# lcd-i2c.net
KiCad netlist of a schematic drawn in EAGLE
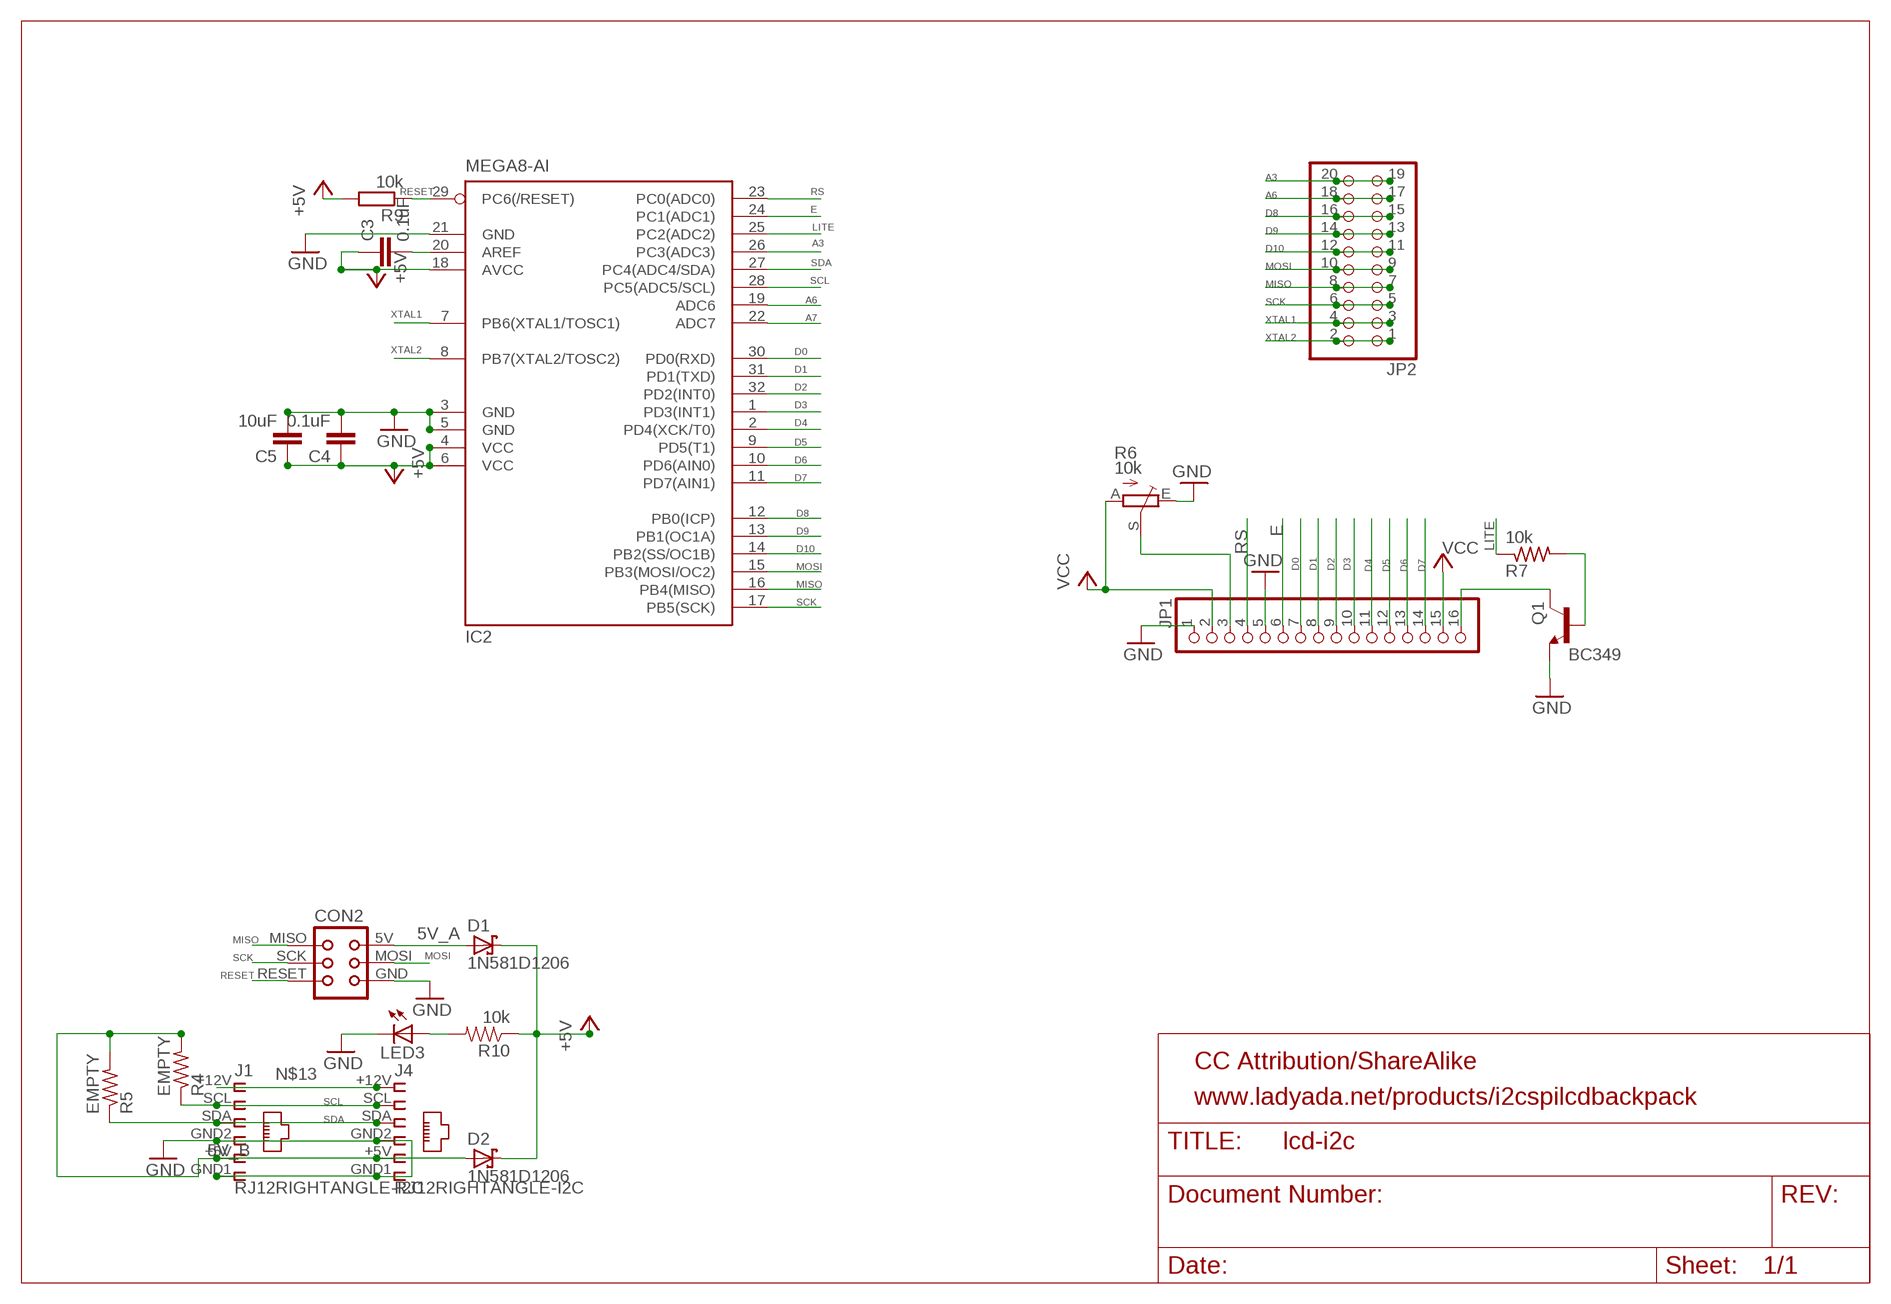
[diagram p0: schematic, sheet 1]

(export (version "E")
  (design (tool "Eeschema 10.0.6"))
  (components
    (comp (ref "C3")
      (value "0.1uF")
      (footprint "eagle-import:C1206")
      (libsource (lib "eagle-import") (part "C-EUC1206"))
    )
    (comp (ref "C4")
      (value "0.1uF")
      (footprint "eagle-import:C1206")
      (libsource (lib "eagle-import") (part "C-EUC1206"))
    )
    (comp (ref "C5")
      (value "10uF")
      (footprint "eagle-import:C1206")
      (libsource (lib "eagle-import") (part "C-EUC1206"))
    )
    (comp (ref "CON2")
      (value "TINYISPTAG")
      (footprint "eagle-import:TC2030-MCP")
      (libsource (lib "eagle-import") (part "TINYISPTAG"))
    )
    (comp (ref "D1")
      (value "1N581D1206")
      (footprint "eagle-import:LED-1206")
      (libsource (lib "eagle-import") (part "1N581D1206"))
    )
    (comp (ref "D2")
      (value "1N581D1206")
      (footprint "eagle-import:LED-1206")
      (libsource (lib "eagle-import") (part "1N581D1206"))
    )
    (comp (ref "IC2")
      (value "MEGA8-AI")
      (footprint "eagle-import:TQFP32-08")
      (fields (field (name "MPN") "ATMEGA8-16AU"))
      (libsource (lib "eagle-import") (part "MEGA8-AI"))
    )
    (comp (ref "J1")
      (value "RJ12RIGHTANGLE-I2C")
      (footprint "eagle-import:RJ12-RIGHTANGLE-I2C")
      (libsource (lib "eagle-import") (part "RJ12RIGHTANGLE-I2C"))
    )
    (comp (ref "J4")
      (value "RJ12RIGHTANGLE-I2C")
      (footprint "eagle-import:RJ12-RIGHTANGLE-I2C")
      (libsource (lib "eagle-import") (part "RJ12RIGHTANGLE-I2C"))
    )
    (comp (ref "JP1")
      (value "PINHD-1X16")
      (footprint "eagle-import:1X16")
      (libsource (lib "eagle-import") (part "PINHD-1X16"))
    )
    (comp (ref "JP2")
      (value "PINHD-2X10")
      (footprint "eagle-import:2X10")
      (libsource (lib "eagle-import") (part "PINHD-2X10"))
    )
    (comp (ref "LED3")
      (value "LEDCHIP-LED0603")
      (footprint "eagle-import:CHIP-LED0603")
      (libsource (lib "eagle-import") (part "LEDCHIP-LED0603"))
    )
    (comp (ref "Q1")
      (value "BC349")
      (footprint "eagle-import:TO92-EBC")
      (libsource (lib "eagle-import") (part "-NPN-TO92-EBCBC317"))
    )
    (comp (ref "R4")
      (value "EMPTY")
      (footprint "eagle-import:M1206")
      (libsource (lib "eagle-import") (part "R-US_M1206"))
    )
    (comp (ref "R5")
      (value "EMPTY")
      (footprint "eagle-import:M1206")
      (libsource (lib "eagle-import") (part "R-US_M1206"))
    )
    (comp (ref "R6")
      (value "10k")
      (footprint "eagle-import:CA6V")
      (libsource (lib "eagle-import") (part "TRIM_EU-CA6V"))
    )
    (comp (ref "R7")
      (value "10k")
      (footprint "eagle-import:M1206")
      (libsource (lib "eagle-import") (part "R-US_M1206"))
    )
    (comp (ref "R9")
      (value "10k")
      (footprint "eagle-import:M1206")
      (libsource (lib "eagle-import") (part "R-EU_M1206"))
    )
    (comp (ref "R10")
      (value "10k")
      (footprint "eagle-import:0603-RES")
      (libsource (lib "eagle-import") (part "RESISTOR0603-RES"))
    )
  )
  (nets
    (net (code "1") (name "+5V") (class "Default")
      (node (ref "C3") (pin "1") (pinfunction "1_1") (pintype "passive"))
      (node (ref "C4") (pin "1") (pinfunction "1_1") (pintype "passive"))
      (node (ref "C5") (pin "1") (pinfunction "1_1") (pintype "passive"))
      (node (ref "D1") (pin "C") (pinfunction "C_C") (pintype "passive"))
      (node (ref "D2") (pin "C") (pinfunction "C_C") (pintype "passive"))
      (node (ref "IC2") (pin "18") (pinfunction "AVCC_18") (pintype "power_in"))
      (node (ref "IC2") (pin "4") (pinfunction "VCC_4") (pintype "power_in"))
      (node (ref "IC2") (pin "6") (pinfunction "VCC_6") (pintype "power_in"))
      (node (ref "R10") (pin "1") (pinfunction "1_1") (pintype "passive"))
      (node (ref "R9") (pin "2") (pinfunction "2_2") (pintype "passive"))
    )
    (net (code "2") (name "/5V_A") (class "Default")
      (node (ref "CON2") (pin "5V") (pinfunction "VCC_5V") (pintype "passive"))
      (node (ref "D1") (pin "A") (pinfunction "A_A") (pintype "passive"))
    )
    (net (code "3") (name "/5V_B") (class "Default")
      (node (ref "D2") (pin "A") (pinfunction "A_A") (pintype "passive"))
      (node (ref "J1") (pin "+5V") (pinfunction "5_+5V") (pintype "power_in"))
      (node (ref "J4") (pin "+5V") (pinfunction "5_+5V") (pintype "power_in"))
      (node (ref "R4") (pin "2") (pinfunction "2_2") (pintype "passive"))
      (node (ref "R5") (pin "2") (pinfunction "2_2") (pintype "passive"))
    )
    (net (code "4") (name "/A3") (class "Default")
      (node (ref "IC2") (pin "26") (pinfunction "PC3(ADC3)_26") (pintype "bidirectional"))
      (node (ref "JP2") (pin "19") (pinfunction "19_19") (pintype "passive"))
      (node (ref "JP2") (pin "20") (pinfunction "20_20") (pintype "passive"))
    )
    (net (code "5") (name "/A6") (class "Default")
      (node (ref "IC2") (pin "19") (pinfunction "ADC6_19") (pintype "bidirectional"))
      (node (ref "JP2") (pin "17") (pinfunction "17_17") (pintype "passive"))
      (node (ref "JP2") (pin "18") (pinfunction "18_18") (pintype "passive"))
    )
    (net (code "6") (name "/A7") (class "Default")
      (node (ref "IC2") (pin "22") (pinfunction "ADC7_22") (pintype "bidirectional"))
    )
    (net (code "7") (name "/D0") (class "Default")
      (node (ref "IC2") (pin "30") (pinfunction "PD0(RXD)_30") (pintype "bidirectional"))
      (node (ref "JP1") (pin "7") (pinfunction "7_7") (pintype "passive"))
    )
    (net (code "8") (name "/D1") (class "Default")
      (node (ref "IC2") (pin "31") (pinfunction "PD1(TXD)_31") (pintype "bidirectional"))
      (node (ref "JP1") (pin "8") (pinfunction "8_8") (pintype "passive"))
    )
    (net (code "9") (name "/D2") (class "Default")
      (node (ref "IC2") (pin "32") (pinfunction "PD2(INT0)_32") (pintype "bidirectional"))
      (node (ref "JP1") (pin "9") (pinfunction "9_9") (pintype "passive"))
    )
    (net (code "10") (name "/D3") (class "Default")
      (node (ref "IC2") (pin "1") (pinfunction "PD3(INT1)_1") (pintype "bidirectional"))
      (node (ref "JP1") (pin "10") (pinfunction "10_10") (pintype "passive"))
    )
    (net (code "11") (name "/D4") (class "Default")
      (node (ref "IC2") (pin "2") (pinfunction "PD4(XCK/T0)_2") (pintype "bidirectional"))
      (node (ref "JP1") (pin "11") (pinfunction "11_11") (pintype "passive"))
    )
    (net (code "12") (name "/D5") (class "Default")
      (node (ref "IC2") (pin "9") (pinfunction "PD5(T1)_9") (pintype "bidirectional"))
      (node (ref "JP1") (pin "12") (pinfunction "12_12") (pintype "passive"))
    )
    (net (code "13") (name "/D6") (class "Default")
      (node (ref "IC2") (pin "10") (pinfunction "PD6(AIN0)_10") (pintype "bidirectional"))
      (node (ref "JP1") (pin "13") (pinfunction "13_13") (pintype "passive"))
    )
    (net (code "14") (name "/D7") (class "Default")
      (node (ref "IC2") (pin "11") (pinfunction "PD7(AIN1)_11") (pintype "bidirectional"))
      (node (ref "JP1") (pin "14") (pinfunction "14_14") (pintype "passive"))
    )
    (net (code "15") (name "/D8") (class "Default")
      (node (ref "IC2") (pin "12") (pinfunction "PB0(ICP)_12") (pintype "bidirectional"))
      (node (ref "JP2") (pin "15") (pinfunction "15_15") (pintype "passive"))
      (node (ref "JP2") (pin "16") (pinfunction "16_16") (pintype "passive"))
    )
    (net (code "16") (name "/D9") (class "Default")
      (node (ref "IC2") (pin "13") (pinfunction "PB1(OC1A)_13") (pintype "bidirectional"))
      (node (ref "JP2") (pin "13") (pinfunction "13_13") (pintype "passive"))
      (node (ref "JP2") (pin "14") (pinfunction "14_14") (pintype "passive"))
    )
    (net (code "17") (name "/D10") (class "Default")
      (node (ref "IC2") (pin "14") (pinfunction "PB2(SS/OC1B)_14") (pintype "bidirectional"))
      (node (ref "JP2") (pin "11") (pinfunction "11_11") (pintype "passive"))
      (node (ref "JP2") (pin "12") (pinfunction "12_12") (pintype "passive"))
    )
    (net (code "18") (name "/E") (class "Default")
      (node (ref "IC2") (pin "24") (pinfunction "PC1(ADC1)_24") (pintype "bidirectional"))
      (node (ref "JP1") (pin "6") (pinfunction "6_6") (pintype "passive"))
    )
    (net (code "19") (name "/LITE") (class "Default")
      (node (ref "IC2") (pin "25") (pinfunction "PC2(ADC2)_25") (pintype "bidirectional"))
      (node (ref "R7") (pin "1") (pinfunction "1_1") (pintype "passive"))
    )
    (net (code "20") (name "/MISO") (class "Default")
      (node (ref "CON2") (pin "MISO") (pinfunction "MISO_MISO") (pintype "passive"))
      (node (ref "IC2") (pin "16") (pinfunction "PB4(MISO)_16") (pintype "bidirectional"))
      (node (ref "JP2") (pin "7") (pinfunction "7_7") (pintype "passive"))
      (node (ref "JP2") (pin "8") (pinfunction "8_8") (pintype "passive"))
    )
    (net (code "21") (name "/MOSI") (class "Default")
      (node (ref "CON2") (pin "MOSI") (pinfunction "MOSI_MOSI") (pintype "passive"))
      (node (ref "IC2") (pin "15") (pinfunction "PB3(MOSI/OC2)_15") (pintype "bidirectional"))
      (node (ref "JP2") (pin "10") (pinfunction "10_10") (pintype "passive"))
      (node (ref "JP2") (pin "9") (pinfunction "9_9") (pintype "passive"))
    )
    (net (code "22") (name "/N$13") (class "Default")
      (node (ref "J1") (pin "+12V") (pinfunction "1_+12V") (pintype "power_in"))
      (node (ref "J4") (pin "+12V") (pinfunction "1_+12V") (pintype "power_in"))
    )
    (net (code "23") (name "/RESET") (class "Default")
      (node (ref "CON2") (pin "RESET") (pinfunction "RESET_RESET") (pintype "passive"))
      (node (ref "IC2") (pin "29") (pinfunction "PC6(/RESET)_29") (pintype "bidirectional"))
      (node (ref "R9") (pin "1") (pinfunction "1_1") (pintype "passive"))
    )
    (net (code "24") (name "/RS") (class "Default")
      (node (ref "IC2") (pin "23") (pinfunction "PC0(ADC0)_23") (pintype "bidirectional"))
      (node (ref "JP1") (pin "4") (pinfunction "4_4") (pintype "passive"))
    )
    (net (code "25") (name "/SCK") (class "Default")
      (node (ref "CON2") (pin "SCK") (pinfunction "SCK_SCK") (pintype "passive"))
      (node (ref "IC2") (pin "17") (pinfunction "PB5(SCK)_17") (pintype "bidirectional"))
      (node (ref "JP2") (pin "5") (pinfunction "5_5") (pintype "passive"))
      (node (ref "JP2") (pin "6") (pinfunction "6_6") (pintype "passive"))
    )
    (net (code "26") (name "/SCL") (class "Default")
      (node (ref "IC2") (pin "28") (pinfunction "PC5(ADC5/SCL)_28") (pintype "bidirectional"))
      (node (ref "J1") (pin "SCL") (pinfunction "2_SCL") (pintype "bidirectional"))
      (node (ref "J4") (pin "SCL") (pinfunction "2_SCL") (pintype "bidirectional"))
      (node (ref "R4") (pin "1") (pinfunction "1_1") (pintype "passive"))
    )
    (net (code "27") (name "/SDA") (class "Default")
      (node (ref "IC2") (pin "27") (pinfunction "PC4(ADC4/SDA)_27") (pintype "bidirectional"))
      (node (ref "J1") (pin "SDA") (pinfunction "3_SDA") (pintype "bidirectional"))
      (node (ref "J4") (pin "SDA") (pinfunction "3_SDA") (pintype "bidirectional"))
      (node (ref "R5") (pin "1") (pinfunction "1_1") (pintype "passive"))
    )
    (net (code "28") (name "/XTAL1") (class "Default")
      (node (ref "IC2") (pin "7") (pinfunction "PB6(XTAL1/TOSC1)_7") (pintype "bidirectional"))
      (node (ref "JP2") (pin "3") (pinfunction "3_3") (pintype "passive"))
      (node (ref "JP2") (pin "4") (pinfunction "4_4") (pintype "passive"))
    )
    (net (code "29") (name "/XTAL2") (class "Default")
      (node (ref "IC2") (pin "8") (pinfunction "PB7(XTAL2/TOSC2)_8") (pintype "bidirectional"))
      (node (ref "JP2") (pin "1") (pinfunction "1_1") (pintype "passive"))
      (node (ref "JP2") (pin "2") (pinfunction "2_2") (pintype "passive"))
    )
    (net (code "30") (name "GND") (class "Default")
      (node (ref "C4") (pin "2") (pinfunction "2_2") (pintype "passive"))
      (node (ref "C5") (pin "2") (pinfunction "2_2") (pintype "passive"))
      (node (ref "CON2") (pin "GND") (pinfunction "GND_GND") (pintype "passive"))
      (node (ref "IC2") (pin "21") (pinfunction "GND_21") (pintype "power_in"))
      (node (ref "IC2") (pin "3") (pinfunction "GND_3") (pintype "power_in"))
      (node (ref "IC2") (pin "5") (pinfunction "GND_5") (pintype "power_in"))
      (node (ref "J1") (pin "GND1") (pinfunction "6_GND1") (pintype "power_in"))
      (node (ref "J1") (pin "GND2") (pinfunction "4_GND2") (pintype "power_in"))
      (node (ref "J4") (pin "GND1") (pinfunction "6_GND1") (pintype "power_in"))
      (node (ref "J4") (pin "GND2") (pinfunction "4_GND2") (pintype "power_in"))
      (node (ref "JP1") (pin "1") (pinfunction "1_1") (pintype "passive"))
      (node (ref "JP1") (pin "5") (pinfunction "5_5") (pintype "passive"))
      (node (ref "LED3") (pin "C") (pinfunction "C_C") (pintype "passive"))
      (node (ref "Q1") (pin "E") (pinfunction "E_E") (pintype "passive"))
      (node (ref "R6") (pin "E") (pinfunction "E_E") (pintype "passive"))
    )
    (net (code "31") (name "Net-(IC2-AREF)") (class "Default")
      (node (ref "C3") (pin "2") (pinfunction "2_2") (pintype "passive"))
      (node (ref "IC2") (pin "20") (pinfunction "AREF_20") (pintype "passive"))
    )
    (net (code "32") (name "Net-(JP1-Pad3)") (class "Default")
      (node (ref "JP1") (pin "3") (pinfunction "3_3") (pintype "passive"))
      (node (ref "R6") (pin "S") (pinfunction "S_S") (pintype "passive"))
    )
    (net (code "33") (name "Net-(JP1-Pad16)") (class "Default")
      (node (ref "JP1") (pin "16") (pinfunction "16_16") (pintype "passive"))
      (node (ref "Q1") (pin "C") (pinfunction "C_C") (pintype "passive"))
    )
    (net (code "34") (name "Net-(LED3-PadA)") (class "Default")
      (node (ref "LED3") (pin "A") (pinfunction "A_A") (pintype "passive"))
      (node (ref "R10") (pin "2") (pinfunction "2_2") (pintype "passive"))
    )
    (net (code "35") (name "Net-(Q1-PadB)") (class "Default")
      (node (ref "Q1") (pin "B") (pinfunction "B_B") (pintype "passive"))
      (node (ref "R7") (pin "2") (pinfunction "2_2") (pintype "passive"))
    )
    (net (code "36") (name "VCC") (class "Default")
      (node (ref "JP1") (pin "15") (pinfunction "15_15") (pintype "passive"))
      (node (ref "JP1") (pin "2") (pinfunction "2_2") (pintype "passive"))
      (node (ref "R6") (pin "A") (pinfunction "A_A") (pintype "passive"))
    )
  )
)
